# DC_IN.net
KiCad netlist of a schematic drawn in Altium Designer
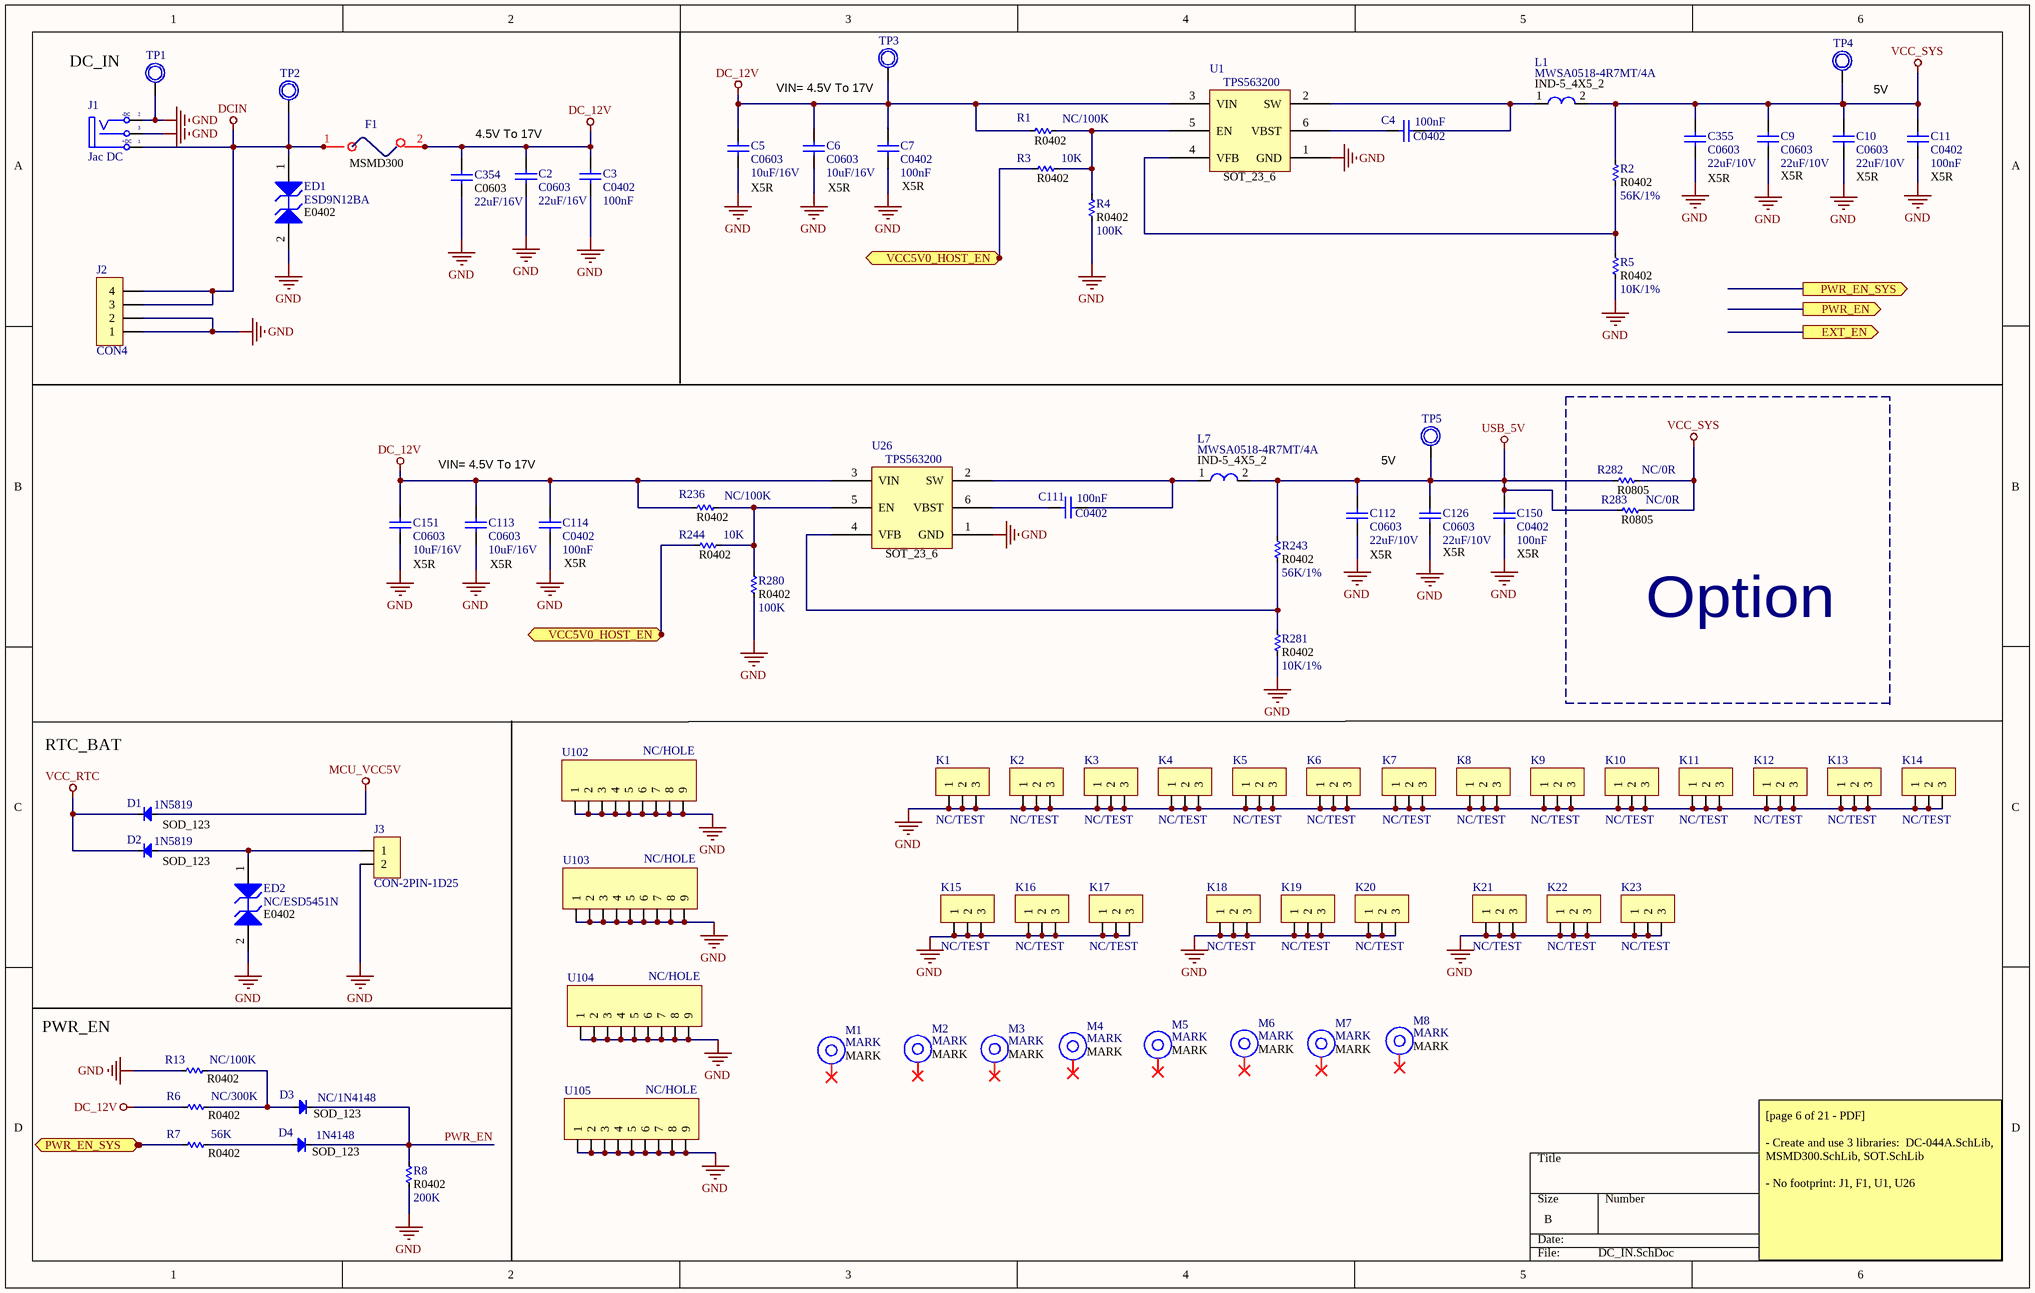
[diagram p0: DC_IN.SchDoc]

(export (version "E")
  (design (tool "Eeschema 10.0.6"))
  (components
    (comp (ref "C2")
      (value "C0603")
      (footprint "C 0603")
      (description "Capacitor")
      (fields (field (name "ALTIUM_VALUE") "22uF/16V") (field (name "PUBLISHER") "Altium Limited"))
      (libsource (lib "Miscellaneous Devices") (part "Cap"))
    )
    (comp (ref "C3")
      (value "C0402")
      (footprint "C 0402")
      (description "Capacitor")
      (fields (field (name "ALTIUM_VALUE") "100nF") (field (name "PUBLISHER") "Altium Limited"))
      (libsource (lib "Miscellaneous Devices") (part "Cap"))
    )
    (comp (ref "C4")
      (value "C0402")
      (footprint "C 0402")
      (description "Capacitor")
      (fields (field (name "ALTIUM_VALUE") "100nF") (field (name "PUBLISHER") "Altium Limited"))
      (libsource (lib "Miscellaneous Devices") (part "Cap"))
    )
    (comp (ref "C5")
      (value "C0603")
      (footprint "C 0603")
      (description "Capacitor")
      (fields
        (field (name "ALTIUM_VALUE") "10uF/16V")
        (field (name "ALTIUM_UNNAMED_1") "X5R")
        (field (name "PUBLISHER") "Altium Limited")
      )
      (libsource (lib "Miscellaneous Devices") (part "Cap"))
    )
    (comp (ref "C6")
      (value "C0603")
      (footprint "C 0603")
      (description "Capacitor")
      (fields
        (field (name "ALTIUM_VALUE") "10uF/16V")
        (field (name "ALTIUM_UNNAMED_1") "X5R")
        (field (name "PUBLISHER") "Altium Limited")
      )
      (libsource (lib "Miscellaneous Devices") (part "Cap"))
    )
    (comp (ref "C7")
      (value "C0402")
      (footprint "C 0402")
      (description "Capacitor")
      (fields
        (field (name "ALTIUM_VALUE") "100nF")
        (field (name "ALTIUM_UNNAMED_1") "X5R")
        (field (name "PUBLISHER") "Altium Limited")
      )
      (libsource (lib "Miscellaneous Devices") (part "Cap"))
    )
    (comp (ref "C9")
      (value "C0603")
      (footprint "C 0603")
      (description "Capacitor")
      (fields
        (field (name "ALTIUM_VALUE") "22uF/10V")
        (field (name "ALTIUM_UNNAMED_1") "X5R")
        (field (name "PUBLISHER") "Altium Limited")
      )
      (libsource (lib "Miscellaneous Devices") (part "Cap"))
    )
    (comp (ref "C10")
      (value "C0603")
      (footprint "C 0603")
      (description "Capacitor")
      (fields
        (field (name "ALTIUM_VALUE") "22uF/10V")
        (field (name "ALTIUM_UNNAMED_1") "X5R")
        (field (name "PUBLISHER") "Altium Limited")
      )
      (libsource (lib "Miscellaneous Devices") (part "Cap"))
    )
    (comp (ref "C11")
      (value "C0402")
      (footprint "C 0402")
      (description "Capacitor")
      (fields
        (field (name "ALTIUM_VALUE") "100nF")
        (field (name "ALTIUM_UNNAMED_1") "X5R")
        (field (name "PUBLISHER") "Altium Limited")
      )
      (libsource (lib "Miscellaneous Devices") (part "Cap"))
    )
    (comp (ref "C111")
      (value "C0402")
      (footprint "C 0402")
      (description "Capacitor")
      (fields (field (name "ALTIUM_VALUE") "100nF") (field (name "PUBLISHER") "Altium Limited"))
      (libsource (lib "Miscellaneous Devices") (part "Cap"))
    )
    (comp (ref "C112")
      (value "C0603")
      (footprint "C 0603")
      (description "Capacitor")
      (fields
        (field (name "ALTIUM_VALUE") "22uF/10V")
        (field (name "ALTIUM_UNNAMED_1") "X5R")
        (field (name "PUBLISHER") "Altium Limited")
      )
      (libsource (lib "Miscellaneous Devices") (part "Cap"))
    )
    (comp (ref "C113")
      (value "C0603")
      (footprint "C 0603")
      (description "Capacitor")
      (fields
        (field (name "ALTIUM_VALUE") "10uF/16V")
        (field (name "ALTIUM_UNNAMED_1") "X5R")
        (field (name "PUBLISHER") "Altium Limited")
      )
      (libsource (lib "Miscellaneous Devices") (part "Cap"))
    )
    (comp (ref "C114")
      (value "C0402")
      (footprint "C 0402")
      (description "Capacitor")
      (fields
        (field (name "ALTIUM_VALUE") "100nF")
        (field (name "ALTIUM_UNNAMED_1") "X5R")
        (field (name "PUBLISHER") "Altium Limited")
      )
      (libsource (lib "Miscellaneous Devices") (part "Cap"))
    )
    (comp (ref "C126")
      (value "C0603")
      (footprint "C 0603")
      (description "Capacitor")
      (fields
        (field (name "ALTIUM_VALUE") "22uF/10V")
        (field (name "ALTIUM_UNNAMED_1") "X5R")
        (field (name "PUBLISHER") "Altium Limited")
      )
      (libsource (lib "Miscellaneous Devices") (part "Cap"))
    )
    (comp (ref "C150")
      (value "C0402")
      (footprint "C 0402")
      (description "Capacitor")
      (fields
        (field (name "ALTIUM_VALUE") "100nF")
        (field (name "ALTIUM_UNNAMED_1") "X5R")
        (field (name "PUBLISHER") "Altium Limited")
      )
      (libsource (lib "Miscellaneous Devices") (part "Cap"))
    )
    (comp (ref "C151")
      (value "C0603")
      (footprint "C 0603")
      (description "Capacitor")
      (fields
        (field (name "ALTIUM_VALUE") "10uF/16V")
        (field (name "ALTIUM_UNNAMED_1") "X5R")
        (field (name "PUBLISHER") "Altium Limited")
      )
      (libsource (lib "Miscellaneous Devices") (part "Cap"))
    )
    (comp (ref "C354")
      (value "C0603")
      (footprint "C 0603")
      (description "Capacitor")
      (fields (field (name "ALTIUM_VALUE") "22uF/16V") (field (name "PUBLISHER") "Altium Limited"))
      (libsource (lib "Miscellaneous Devices") (part "Cap"))
    )
    (comp (ref "C355")
      (value "C0603")
      (footprint "C 0603")
      (description "Capacitor")
      (fields
        (field (name "ALTIUM_VALUE") "22uF/10V")
        (field (name "ALTIUM_UNNAMED_1") "X5R")
        (field (name "PUBLISHER") "Altium Limited")
      )
      (libsource (lib "Miscellaneous Devices") (part "Cap"))
    )
    (comp (ref "D1")
      (value "1N5819")
      (footprint "DIO-SMD-123")
      (description "Default Diode")
      (fields
        (field (name "TYPR") "SOD_123")
        (field (name "Comment") "Diode SMD")
        (field (name "PUBLISHER") "Altium Limited")
      )
      (libsource (lib "LIBRARY") (part "Diode SMD"))
    )
    (comp (ref "D2")
      (value "1N5819")
      (footprint "DIO-SMD-123")
      (description "Default Diode")
      (fields
        (field (name "TYPR") "SOD_123")
        (field (name "Comment") "Diode SMD")
        (field (name "PUBLISHER") "Altium Limited")
      )
      (libsource (lib "LIBRARY") (part "Diode SMD"))
    )
    (comp (ref "D3")
      (value "NC/1N4148")
      (footprint "DIO-SMD-123")
      (description "Default Diode")
      (fields
        (field (name "TYPR") "SOD_123")
        (field (name "Comment") "Diode SMD")
        (field (name "PUBLISHER") "Altium Limited")
      )
      (libsource (lib "LIBRARY") (part "Diode SMD"))
    )
    (comp (ref "D4")
      (value "1N4148")
      (footprint "DIO-SMD-123")
      (description "Default Diode")
      (fields
        (field (name "TYPR") "SOD_123")
        (field (name "Comment") "Diode SMD")
        (field (name "PUBLISHER") "Altium Limited")
      )
      (libsource (lib "LIBRARY") (part "Diode SMD"))
    )
    (comp (ref "ED1")
      (value "ESD9N12BA")
      (footprint "DFN1006:DFN1006-2L")
      (description "600 W Peak Power Zener Transient Voltage Suppressor, Bidirectional, 2-Pin SMB, Tape and Reel")
      (fields
        (field (name "MANUFACTURER") "On Semiconductor")
        (field (name "PARTNUMBER") "1SMB54CAT3")
        (field (name "SIZE") "E0402")
      )
      (libsource (lib "ON Semi Transient Voltage Suppressors (TVS)") (part "1SMB54CAT3"))
    )
    (comp (ref "ED2")
      (value "NC/ESD5451N")
      (footprint "DFN1006:DFN1006-2L")
      (description "600 W Peak Power Zener Transient Voltage Suppressor, Bidirectional, 2-Pin SMB, Tape and Reel")
      (fields
        (field (name "MANUFACTURER") "On Semiconductor")
        (field (name "PARTNUMBER") "1SMB54CAT3")
        (field (name "SIZE") "E0402")
      )
      (libsource (lib "ON Semi Transient Voltage Suppressors (TVS)") (part "1SMB54CAT3"))
    )
    (comp (ref "F1") (value "mSMD300") (footprint "MSMD300/3A") (libsource (lib "Schlib2") (part "mSMD300")))
    (comp (ref "J1")
      (value "Jac DC")
      (footprint "DC-IN")
      (description "Jac DC input")
      (libsource (lib "syhaunguyen") (part "DCIN"))
    )
    (comp (ref "J2")
      (value "CON4")
      (footprint "CON4")
      (description "WR-PHD 2.00 mm Socket Header")
      (fields
        (field (name "MANUFACTURER") "Würth Elektronik eiSos GmbH")
        (field (name "PARTNO") "62000411821")
        (field (name "CREATED BY") "Karrer Zheng")
      )
      (libsource (lib "LIBRARY") (part "JP4x1-2.0"))
    )
    (comp (ref "J3")
      (value "CON-2PIN-1D25")
      (footprint "Header2")
      (description "WR-PHD 2.54 mm Angled Socket Header")
      (fields
        (field (name "MANUFACTURER") "Würth Elektronik eiSos GmbH")
        (field (name "PARTNO") "613002143121")
        (field (name "CREATED BY") "Karrer Zheng")
      )
      (libsource (lib "LIBRARY") (part "JP2"))
    )
    (comp (ref "K1")
      (value "NC/TEST")
      (footprint "KTest")
      (description "WR-PHD 2.54 mm Angled Socket Header")
      (fields
        (field (name "MANUFACTURER") "Würth Elektronik eiSos GmbH")
        (field (name "PARTNO") "613003143121")
        (field (name "CREATED BY") "Karrer Zheng")
      )
      (libsource (lib "LIBRARY") (part "JP3"))
    )
    (comp (ref "K2")
      (value "NC/TEST")
      (footprint "KTest")
      (description "WR-PHD 2.54 mm Angled Socket Header")
      (fields
        (field (name "MANUFACTURER") "Würth Elektronik eiSos GmbH")
        (field (name "PARTNO") "613003143121")
        (field (name "CREATED BY") "Karrer Zheng")
      )
      (libsource (lib "LIBRARY") (part "JP3"))
    )
    (comp (ref "K3")
      (value "NC/TEST")
      (footprint "KTest")
      (description "WR-PHD 2.54 mm Angled Socket Header")
      (fields
        (field (name "MANUFACTURER") "Würth Elektronik eiSos GmbH")
        (field (name "PARTNO") "613003143121")
        (field (name "CREATED BY") "Karrer Zheng")
      )
      (libsource (lib "LIBRARY") (part "JP3"))
    )
    (comp (ref "K4")
      (value "NC/TEST")
      (footprint "KTest")
      (description "WR-PHD 2.54 mm Angled Socket Header")
      (fields
        (field (name "MANUFACTURER") "Würth Elektronik eiSos GmbH")
        (field (name "PARTNO") "613003143121")
        (field (name "CREATED BY") "Karrer Zheng")
      )
      (libsource (lib "LIBRARY") (part "JP3"))
    )
    (comp (ref "K5")
      (value "NC/TEST")
      (footprint "KTest")
      (description "WR-PHD 2.54 mm Angled Socket Header")
      (fields
        (field (name "MANUFACTURER") "Würth Elektronik eiSos GmbH")
        (field (name "PARTNO") "613003143121")
        (field (name "CREATED BY") "Karrer Zheng")
      )
      (libsource (lib "LIBRARY") (part "JP3"))
    )
    (comp (ref "K6")
      (value "NC/TEST")
      (footprint "KTest")
      (description "WR-PHD 2.54 mm Angled Socket Header")
      (fields
        (field (name "MANUFACTURER") "Würth Elektronik eiSos GmbH")
        (field (name "PARTNO") "613003143121")
        (field (name "CREATED BY") "Karrer Zheng")
      )
      (libsource (lib "LIBRARY") (part "JP3"))
    )
    (comp (ref "K7")
      (value "NC/TEST")
      (footprint "KTest")
      (description "WR-PHD 2.54 mm Angled Socket Header")
      (fields
        (field (name "MANUFACTURER") "Würth Elektronik eiSos GmbH")
        (field (name "PARTNO") "613003143121")
        (field (name "CREATED BY") "Karrer Zheng")
      )
      (libsource (lib "LIBRARY") (part "JP3"))
    )
    (comp (ref "K8")
      (value "NC/TEST")
      (footprint "KTest")
      (description "WR-PHD 2.54 mm Angled Socket Header")
      (fields
        (field (name "MANUFACTURER") "Würth Elektronik eiSos GmbH")
        (field (name "PARTNO") "613003143121")
        (field (name "CREATED BY") "Karrer Zheng")
      )
      (libsource (lib "LIBRARY") (part "JP3"))
    )
    (comp (ref "K9")
      (value "NC/TEST")
      (footprint "KTest")
      (description "WR-PHD 2.54 mm Angled Socket Header")
      (fields
        (field (name "MANUFACTURER") "Würth Elektronik eiSos GmbH")
        (field (name "PARTNO") "613003143121")
        (field (name "CREATED BY") "Karrer Zheng")
      )
      (libsource (lib "LIBRARY") (part "JP3"))
    )
    (comp (ref "K10")
      (value "NC/TEST")
      (footprint "KTest")
      (description "WR-PHD 2.54 mm Angled Socket Header")
      (fields
        (field (name "MANUFACTURER") "Würth Elektronik eiSos GmbH")
        (field (name "PARTNO") "613003143121")
        (field (name "CREATED BY") "Karrer Zheng")
      )
      (libsource (lib "LIBRARY") (part "JP3"))
    )
    (comp (ref "K11")
      (value "NC/TEST")
      (footprint "KTest")
      (description "WR-PHD 2.54 mm Angled Socket Header")
      (fields
        (field (name "MANUFACTURER") "Würth Elektronik eiSos GmbH")
        (field (name "PARTNO") "613003143121")
        (field (name "CREATED BY") "Karrer Zheng")
      )
      (libsource (lib "LIBRARY") (part "JP3"))
    )
    (comp (ref "K12")
      (value "NC/TEST")
      (footprint "KTest")
      (description "WR-PHD 2.54 mm Angled Socket Header")
      (fields
        (field (name "MANUFACTURER") "Würth Elektronik eiSos GmbH")
        (field (name "PARTNO") "613003143121")
        (field (name "CREATED BY") "Karrer Zheng")
      )
      (libsource (lib "LIBRARY") (part "JP3"))
    )
    (comp (ref "K13")
      (value "NC/TEST")
      (footprint "KTest")
      (description "WR-PHD 2.54 mm Angled Socket Header")
      (fields
        (field (name "MANUFACTURER") "Würth Elektronik eiSos GmbH")
        (field (name "PARTNO") "613003143121")
        (field (name "CREATED BY") "Karrer Zheng")
      )
      (libsource (lib "LIBRARY") (part "JP3"))
    )
    (comp (ref "K14")
      (value "NC/TEST")
      (footprint "KTest")
      (description "WR-PHD 2.54 mm Angled Socket Header")
      (fields
        (field (name "MANUFACTURER") "Würth Elektronik eiSos GmbH")
        (field (name "PARTNO") "613003143121")
        (field (name "CREATED BY") "Karrer Zheng")
      )
      (libsource (lib "LIBRARY") (part "JP3"))
    )
    (comp (ref "K15")
      (value "NC/TEST")
      (footprint "KTest")
      (description "WR-PHD 2.54 mm Angled Socket Header")
      (fields
        (field (name "MANUFACTURER") "Würth Elektronik eiSos GmbH")
        (field (name "PARTNO") "613003143121")
        (field (name "CREATED BY") "Karrer Zheng")
      )
      (libsource (lib "LIBRARY") (part "JP3"))
    )
    (comp (ref "K16")
      (value "NC/TEST")
      (footprint "KTest")
      (description "WR-PHD 2.54 mm Angled Socket Header")
      (fields
        (field (name "MANUFACTURER") "Würth Elektronik eiSos GmbH")
        (field (name "PARTNO") "613003143121")
        (field (name "CREATED BY") "Karrer Zheng")
      )
      (libsource (lib "LIBRARY") (part "JP3"))
    )
    (comp (ref "K17")
      (value "NC/TEST")
      (footprint "KTest")
      (description "WR-PHD 2.54 mm Angled Socket Header")
      (fields
        (field (name "MANUFACTURER") "Würth Elektronik eiSos GmbH")
        (field (name "PARTNO") "613003143121")
        (field (name "CREATED BY") "Karrer Zheng")
      )
      (libsource (lib "LIBRARY") (part "JP3"))
    )
    (comp (ref "K18")
      (value "NC/TEST")
      (footprint "KTest")
      (description "WR-PHD 2.54 mm Angled Socket Header")
      (fields
        (field (name "MANUFACTURER") "Würth Elektronik eiSos GmbH")
        (field (name "PARTNO") "613003143121")
        (field (name "CREATED BY") "Karrer Zheng")
      )
      (libsource (lib "LIBRARY") (part "JP3"))
    )
    (comp (ref "K19")
      (value "NC/TEST")
      (footprint "KTest")
      (description "WR-PHD 2.54 mm Angled Socket Header")
      (fields
        (field (name "MANUFACTURER") "Würth Elektronik eiSos GmbH")
        (field (name "PARTNO") "613003143121")
        (field (name "CREATED BY") "Karrer Zheng")
      )
      (libsource (lib "LIBRARY") (part "JP3"))
    )
    (comp (ref "K20")
      (value "NC/TEST")
      (footprint "KTest")
      (description "WR-PHD 2.54 mm Angled Socket Header")
      (fields
        (field (name "MANUFACTURER") "Würth Elektronik eiSos GmbH")
        (field (name "PARTNO") "613003143121")
        (field (name "CREATED BY") "Karrer Zheng")
      )
      (libsource (lib "LIBRARY") (part "JP3"))
    )
    (comp (ref "K21")
      (value "NC/TEST")
      (footprint "KTest")
      (description "WR-PHD 2.54 mm Angled Socket Header")
      (fields
        (field (name "MANUFACTURER") "Würth Elektronik eiSos GmbH")
        (field (name "PARTNO") "613003143121")
        (field (name "CREATED BY") "Karrer Zheng")
      )
      (libsource (lib "LIBRARY") (part "JP3"))
    )
    (comp (ref "K22")
      (value "NC/TEST")
      (footprint "KTest")
      (description "WR-PHD 2.54 mm Angled Socket Header")
      (fields
        (field (name "MANUFACTURER") "Würth Elektronik eiSos GmbH")
        (field (name "PARTNO") "613003143121")
        (field (name "CREATED BY") "Karrer Zheng")
      )
      (libsource (lib "LIBRARY") (part "JP3"))
    )
    (comp (ref "K23")
      (value "NC/TEST")
      (footprint "KTest")
      (description "WR-PHD 2.54 mm Angled Socket Header")
      (fields
        (field (name "MANUFACTURER") "Würth Elektronik eiSos GmbH")
        (field (name "PARTNO") "613003143121")
        (field (name "CREATED BY") "Karrer Zheng")
      )
      (libsource (lib "LIBRARY") (part "JP3"))
    )
    (comp (ref "L1")
      (value "MWSA0518-4R7MT/4A")
      (footprint "L-SMD-M-7.3x4.5")
      (fields
        (field (name "PARTNO") "78477010")
        (field (name "MANUFACTURER") "Wurth Elektronik")
        (field (name "ALTIUM_UNNAMED_1") "IND-5_4X5_2")
        (field (name "CREATED BY") "Baojun Chen")
      )
      (libsource (lib "LIBRARY") (part "L-SMD-1"))
    )
    (comp (ref "L7")
      (value "MWSA0518-4R7MT/4A")
      (footprint "L-SMD-M-7.3x4.5")
      (fields
        (field (name "PARTNO") "78477010")
        (field (name "MANUFACTURER") "Wurth Elektronik")
        (field (name "ALTIUM_UNNAMED_1") "IND-5_4X5_2")
        (field (name "CREATED BY") "Baojun Chen")
      )
      (libsource (lib "LIBRARY") (part "L-SMD-1"))
    )
    (comp (ref "M1") (value "MARK") (libsource (lib "SOT") (part "MARK")))
    (comp (ref "M2") (value "MARK") (libsource (lib "SOT") (part "MARK")))
    (comp (ref "M3") (value "MARK") (libsource (lib "SOT") (part "MARK")))
    (comp (ref "M4") (value "MARK") (libsource (lib "SOT") (part "MARK")))
    (comp (ref "M5") (value "MARK") (libsource (lib "SOT") (part "MARK")))
    (comp (ref "M6") (value "MARK") (libsource (lib "SOT") (part "MARK")))
    (comp (ref "M7") (value "MARK") (libsource (lib "SOT") (part "MARK")))
    (comp (ref "M8") (value "MARK") (libsource (lib "SOT") (part "MARK")))
    (comp (ref "R1")
      (value "R0402")
      (footprint "R 0402")
      (description "Resistor")
      (fields
        (field (name "MANUFACTURER") "Generic Components")
        (field (name "ALTIUM_VALUE") "NC/100K")
        (field (name "PUBLISHER") "Altium Hobart Technology Centre")
      )
      (libsource (lib "LIBRARY") (part "Res-SMD"))
    )
    (comp (ref "R2")
      (value "R0402")
      (footprint "R 0402")
      (description "Resistor")
      (fields
        (field (name "MANUFACTURER") "Generic Components")
        (field (name "ALTIUM_VALUE") "56K/1%")
        (field (name "PUBLISHER") "Altium Hobart Technology Centre")
      )
      (libsource (lib "LIBRARY") (part "Res-SMD"))
    )
    (comp (ref "R3")
      (value "R0402")
      (footprint "R 0402")
      (description "Resistor")
      (fields
        (field (name "MANUFACTURER") "Generic Components")
        (field (name "ALTIUM_VALUE") "10K")
        (field (name "PUBLISHER") "Altium Hobart Technology Centre")
      )
      (libsource (lib "LIBRARY") (part "Res-SMD"))
    )
    (comp (ref "R4")
      (value "R0402")
      (footprint "R 0402")
      (description "Resistor")
      (fields
        (field (name "MANUFACTURER") "Generic Components")
        (field (name "ALTIUM_VALUE") "100K")
        (field (name "PUBLISHER") "Altium Hobart Technology Centre")
      )
      (libsource (lib "LIBRARY") (part "Res-SMD"))
    )
    (comp (ref "R5")
      (value "R0402")
      (footprint "R 0402")
      (description "Resistor")
      (fields
        (field (name "MANUFACTURER") "Generic Components")
        (field (name "ALTIUM_VALUE") "10K/1%")
        (field (name "PUBLISHER") "Altium Hobart Technology Centre")
      )
      (libsource (lib "LIBRARY") (part "Res-SMD"))
    )
    (comp (ref "R6")
      (value "R0402")
      (footprint "R 0402")
      (description "Resistor")
      (fields
        (field (name "MANUFACTURER") "Generic Components")
        (field (name "ALTIUM_VALUE") "NC/300K")
        (field (name "PUBLISHER") "Altium Hobart Technology Centre")
      )
      (libsource (lib "LIBRARY") (part "Res-SMD"))
    )
    (comp (ref "R7")
      (value "R0402")
      (footprint "R 0402")
      (description "Resistor")
      (fields
        (field (name "MANUFACTURER") "Generic Components")
        (field (name "ALTIUM_VALUE") "56K")
        (field (name "PUBLISHER") "Altium Hobart Technology Centre")
      )
      (libsource (lib "LIBRARY") (part "Res-SMD"))
    )
    (comp (ref "R8")
      (value "R0402")
      (footprint "R 0402")
      (description "Resistor")
      (fields
        (field (name "MANUFACTURER") "Generic Components")
        (field (name "ALTIUM_VALUE") "200K")
        (field (name "PUBLISHER") "Altium Hobart Technology Centre")
      )
      (libsource (lib "LIBRARY") (part "Res-SMD"))
    )
    (comp (ref "R13")
      (value "R0402")
      (footprint "R 0402")
      (description "Resistor")
      (fields
        (field (name "MANUFACTURER") "Generic Components")
        (field (name "ALTIUM_VALUE") "NC/100K")
        (field (name "PUBLISHER") "Altium Hobart Technology Centre")
      )
      (libsource (lib "LIBRARY") (part "Res-SMD"))
    )
    (comp (ref "R236")
      (value "R0402")
      (footprint "R 0402")
      (description "Resistor")
      (fields
        (field (name "MANUFACTURER") "Generic Components")
        (field (name "ALTIUM_VALUE") "NC/100K")
        (field (name "PUBLISHER") "Altium Hobart Technology Centre")
      )
      (libsource (lib "LIBRARY") (part "Res-SMD"))
    )
    (comp (ref "R243")
      (value "R0402")
      (footprint "R 0402")
      (description "Resistor")
      (fields
        (field (name "MANUFACTURER") "Generic Components")
        (field (name "ALTIUM_VALUE") "56K/1%")
        (field (name "PUBLISHER") "Altium Hobart Technology Centre")
      )
      (libsource (lib "LIBRARY") (part "Res-SMD"))
    )
    (comp (ref "R244")
      (value "R0402")
      (footprint "R 0402")
      (description "Resistor")
      (fields
        (field (name "MANUFACTURER") "Generic Components")
        (field (name "ALTIUM_VALUE") "10K")
        (field (name "PUBLISHER") "Altium Hobart Technology Centre")
      )
      (libsource (lib "LIBRARY") (part "Res-SMD"))
    )
    (comp (ref "R280")
      (value "R0402")
      (footprint "R 0402")
      (description "Resistor")
      (fields
        (field (name "MANUFACTURER") "Generic Components")
        (field (name "ALTIUM_VALUE") "100K")
        (field (name "PUBLISHER") "Altium Hobart Technology Centre")
      )
      (libsource (lib "LIBRARY") (part "Res-SMD"))
    )
    (comp (ref "R281")
      (value "R0402")
      (footprint "R 0402")
      (description "Resistor")
      (fields
        (field (name "MANUFACTURER") "Generic Components")
        (field (name "ALTIUM_VALUE") "10K/1%")
        (field (name "PUBLISHER") "Altium Hobart Technology Centre")
      )
      (libsource (lib "LIBRARY") (part "Res-SMD"))
    )
    (comp (ref "R282")
      (value "R0805")
      (footprint "R 0805")
      (description "Resistor")
      (fields
        (field (name "MANUFACTURER") "Generic Components")
        (field (name "ALTIUM_VALUE") "NC/0R")
        (field (name "PUBLISHER") "Altium Hobart Technology Centre")
      )
      (libsource (lib "LIBRARY") (part "Res-SMD"))
    )
    (comp (ref "R283")
      (value "R0805")
      (footprint "R 0805")
      (description "Resistor")
      (fields
        (field (name "MANUFACTURER") "Generic Components")
        (field (name "ALTIUM_VALUE") "NC/0R")
        (field (name "PUBLISHER") "Altium Hobart Technology Centre")
      )
      (libsource (lib "LIBRARY") (part "Res-SMD"))
    )
    (comp (ref "TP1")
      (value "TP")
      (footprint "TP1")
      (description "Test Point")
      (libsource (lib "syhaunguyen") (part "TP1"))
    )
    (comp (ref "TP2")
      (value "TP")
      (footprint "TP1")
      (description "Test Point")
      (libsource (lib "syhaunguyen") (part "TP1"))
    )
    (comp (ref "TP3")
      (value "TP")
      (footprint "TP1")
      (description "Test Point")
      (libsource (lib "syhaunguyen") (part "TP1"))
    )
    (comp (ref "TP4")
      (value "TP")
      (footprint "TP1")
      (description "Test Point")
      (libsource (lib "syhaunguyen") (part "TP1"))
    )
    (comp (ref "TP5")
      (value "TP")
      (footprint "TP1")
      (description "Test Point")
      (libsource (lib "syhaunguyen") (part "TP1"))
    )
    (comp (ref "U1")
      (value "SOT-23-6_TPS563200")
      (footprint "SOT:SOT-23-6")
      (description "Switching Voltage Regulators 17 Vin,3A Sync SD Reg")
      (fields
        (field (name "MANUFACTURER") "Texas Instruments")
        (field (name "MANUFACTURER PART NUMBER") "TPS563200DDCR")
      )
      (libsource (lib "SOT") (part "SOT-23-6_TPS563200"))
    )
    (comp (ref "U26")
      (value "SOT-23-6_TPS563200")
      (footprint "SOT:SOT-23-6")
      (description "Switching Voltage Regulators 17 Vin,3A Sync SD Reg")
      (fields
        (field (name "MANUFACTURER") "Texas Instruments")
        (field (name "MANUFACTURER PART NUMBER") "TPS563200DDCR")
      )
      (libsource (lib "SOT") (part "SOT-23-6_TPS563200"))
    )
    (comp (ref "U102")
      (value "NC/HOLE")
      (footprint "JP9-C1T")
      (description "WR-PHD 2.54 mm Angled Socket Header")
      (fields
        (field (name "MANUFACTURER") "Würth Elektronik eiSos GmbH")
        (field (name "PARTNO") "613009143121")
        (field (name "CREATED BY") "Karrer Zheng")
      )
      (libsource (lib "LIBRARY") (part "JP9"))
    )
    (comp (ref "U103")
      (value "NC/HOLE")
      (footprint "JP9-C1T")
      (description "WR-PHD 2.54 mm Angled Socket Header")
      (fields
        (field (name "MANUFACTURER") "Würth Elektronik eiSos GmbH")
        (field (name "PARTNO") "613009143121")
        (field (name "CREATED BY") "Karrer Zheng")
      )
      (libsource (lib "LIBRARY") (part "JP9"))
    )
    (comp (ref "U104")
      (value "NC/HOLE")
      (footprint "JP9-C1T")
      (description "WR-PHD 2.54 mm Angled Socket Header")
      (fields
        (field (name "MANUFACTURER") "Würth Elektronik eiSos GmbH")
        (field (name "PARTNO") "613009143121")
        (field (name "CREATED BY") "Karrer Zheng")
      )
      (libsource (lib "LIBRARY") (part "JP9"))
    )
    (comp (ref "U105")
      (value "NC/HOLE")
      (footprint "JP9-C1T")
      (description "WR-PHD 2.54 mm Angled Socket Header")
      (fields
        (field (name "MANUFACTURER") "Würth Elektronik eiSos GmbH")
        (field (name "PARTNO") "613009143121")
        (field (name "CREATED BY") "Karrer Zheng")
      )
      (libsource (lib "LIBRARY") (part "JP9"))
    )
  )
  (nets
    (net (code "2") (name "/PWR_EN") (class "Default")
      (node (ref "D3") (pin "2") (pinfunction "K_2") (pintype "passive"))
      (node (ref "D4") (pin "2") (pinfunction "K_2") (pintype "passive"))
      (node (ref "R8") (pin "1") (pinfunction "1_1") (pintype "passive"))
    )
    (net (code "3") (name "/PWR_EN_SYS") (class "Default")
      (node (ref "R7") (pin "2") (pinfunction "2_2") (pintype "passive"))
    )
    (net (code "5") (name "DCIN") (class "Default")
      (node (ref "ED1") (pin "1") (pinfunction "A1_1") (pintype "passive"))
      (node (ref "F1") (pin "1") (pinfunction "1_1") (pintype "passive"))
      (node (ref "J1") (pin "1") (pinfunction "T_1") (pintype "passive"))
      (node (ref "J2") (pin "3") (pinfunction "3_3") (pintype "passive"))
      (node (ref "J2") (pin "4") (pinfunction "4_4") (pintype "passive"))
      (node (ref "TP2") (pin "1") (pinfunction "1_1") (pintype "passive"))
    )
    (net (code "6") (name "DC_12V") (class "Default")
      (node (ref "C113") (pin "2") (pinfunction "2_2") (pintype "passive"))
      (node (ref "C114") (pin "2") (pinfunction "2_2") (pintype "passive"))
      (node (ref "C151") (pin "2") (pinfunction "2_2") (pintype "passive"))
      (node (ref "C2") (pin "2") (pinfunction "2_2") (pintype "passive"))
      (node (ref "C3") (pin "2") (pinfunction "2_2") (pintype "passive"))
      (node (ref "C354") (pin "2") (pinfunction "2_2") (pintype "passive"))
      (node (ref "C5") (pin "2") (pinfunction "2_2") (pintype "passive"))
      (node (ref "C6") (pin "2") (pinfunction "2_2") (pintype "passive"))
      (node (ref "C7") (pin "2") (pinfunction "2_2") (pintype "passive"))
      (node (ref "F1") (pin "2") (pinfunction "2_2") (pintype "passive"))
      (node (ref "R1") (pin "2") (pinfunction "2_2") (pintype "passive"))
      (node (ref "R236") (pin "2") (pinfunction "2_2") (pintype "passive"))
      (node (ref "R6") (pin "2") (pinfunction "2_2") (pintype "passive"))
      (node (ref "TP3") (pin "1") (pinfunction "1_1") (pintype "passive"))
      (node (ref "U1") (pin "3") (pinfunction "VIN_3") (pintype "passive"))
      (node (ref "U26") (pin "3") (pinfunction "VIN_3") (pintype "passive"))
    )
    (net (code "7") (name "GND") (class "Default")
      (node (ref "C10") (pin "1") (pinfunction "1_1") (pintype "passive"))
      (node (ref "C11") (pin "1") (pinfunction "1_1") (pintype "passive"))
      (node (ref "C112") (pin "1") (pinfunction "1_1") (pintype "passive"))
      (node (ref "C113") (pin "1") (pinfunction "1_1") (pintype "passive"))
      (node (ref "C114") (pin "1") (pinfunction "1_1") (pintype "passive"))
      (node (ref "C126") (pin "1") (pinfunction "1_1") (pintype "passive"))
      (node (ref "C150") (pin "1") (pinfunction "1_1") (pintype "passive"))
      (node (ref "C151") (pin "1") (pinfunction "1_1") (pintype "passive"))
      (node (ref "C2") (pin "1") (pinfunction "1_1") (pintype "passive"))
      (node (ref "C3") (pin "1") (pinfunction "1_1") (pintype "passive"))
      (node (ref "C354") (pin "1") (pinfunction "1_1") (pintype "passive"))
      (node (ref "C355") (pin "1") (pinfunction "1_1") (pintype "passive"))
      (node (ref "C5") (pin "1") (pinfunction "1_1") (pintype "passive"))
      (node (ref "C6") (pin "1") (pinfunction "1_1") (pintype "passive"))
      (node (ref "C7") (pin "1") (pinfunction "1_1") (pintype "passive"))
      (node (ref "C9") (pin "1") (pinfunction "1_1") (pintype "passive"))
      (node (ref "ED1") (pin "2") (pinfunction "A2_2") (pintype "passive"))
      (node (ref "ED2") (pin "2") (pinfunction "A2_2") (pintype "passive"))
      (node (ref "J1") (pin "2") (pinfunction "TN_2") (pintype "passive"))
      (node (ref "J1") (pin "3") (pinfunction "S_3") (pintype "power_in"))
      (node (ref "J2") (pin "1") (pinfunction "1_1") (pintype "passive"))
      (node (ref "J2") (pin "2") (pinfunction "2_2") (pintype "passive"))
      (node (ref "J3") (pin "2") (pinfunction "2_2") (pintype "passive"))
      (node (ref "K1") (pin "1") (pinfunction "1_1") (pintype "passive"))
      (node (ref "K1") (pin "2") (pinfunction "2_2") (pintype "passive"))
      (node (ref "K1") (pin "3") (pinfunction "3_3") (pintype "passive"))
      (node (ref "K10") (pin "1") (pinfunction "1_1") (pintype "passive"))
      (node (ref "K10") (pin "2") (pinfunction "2_2") (pintype "passive"))
      (node (ref "K10") (pin "3") (pinfunction "3_3") (pintype "passive"))
      (node (ref "K11") (pin "1") (pinfunction "1_1") (pintype "passive"))
      (node (ref "K11") (pin "2") (pinfunction "2_2") (pintype "passive"))
      (node (ref "K11") (pin "3") (pinfunction "3_3") (pintype "passive"))
      (node (ref "K12") (pin "1") (pinfunction "1_1") (pintype "passive"))
      (node (ref "K12") (pin "2") (pinfunction "2_2") (pintype "passive"))
      (node (ref "K12") (pin "3") (pinfunction "3_3") (pintype "passive"))
      (node (ref "K13") (pin "1") (pinfunction "1_1") (pintype "passive"))
      (node (ref "K13") (pin "2") (pinfunction "2_2") (pintype "passive"))
      (node (ref "K13") (pin "3") (pinfunction "3_3") (pintype "passive"))
      (node (ref "K14") (pin "1") (pinfunction "1_1") (pintype "passive"))
      (node (ref "K14") (pin "2") (pinfunction "2_2") (pintype "passive"))
      (node (ref "K14") (pin "3") (pinfunction "3_3") (pintype "passive"))
      (node (ref "K15") (pin "1") (pinfunction "1_1") (pintype "passive"))
      (node (ref "K15") (pin "2") (pinfunction "2_2") (pintype "passive"))
      (node (ref "K15") (pin "3") (pinfunction "3_3") (pintype "passive"))
      (node (ref "K16") (pin "1") (pinfunction "1_1") (pintype "passive"))
      (node (ref "K16") (pin "2") (pinfunction "2_2") (pintype "passive"))
      (node (ref "K16") (pin "3") (pinfunction "3_3") (pintype "passive"))
      (node (ref "K17") (pin "1") (pinfunction "1_1") (pintype "passive"))
      (node (ref "K17") (pin "2") (pinfunction "2_2") (pintype "passive"))
      (node (ref "K17") (pin "3") (pinfunction "3_3") (pintype "passive"))
      (node (ref "K18") (pin "1") (pinfunction "1_1") (pintype "passive"))
      (node (ref "K18") (pin "2") (pinfunction "2_2") (pintype "passive"))
      (node (ref "K18") (pin "3") (pinfunction "3_3") (pintype "passive"))
      (node (ref "K19") (pin "1") (pinfunction "1_1") (pintype "passive"))
      (node (ref "K19") (pin "2") (pinfunction "2_2") (pintype "passive"))
      (node (ref "K19") (pin "3") (pinfunction "3_3") (pintype "passive"))
      (node (ref "K2") (pin "1") (pinfunction "1_1") (pintype "passive"))
      (node (ref "K2") (pin "2") (pinfunction "2_2") (pintype "passive"))
      (node (ref "K2") (pin "3") (pinfunction "3_3") (pintype "passive"))
      (node (ref "K20") (pin "1") (pinfunction "1_1") (pintype "passive"))
      (node (ref "K20") (pin "2") (pinfunction "2_2") (pintype "passive"))
      (node (ref "K20") (pin "3") (pinfunction "3_3") (pintype "passive"))
      (node (ref "K21") (pin "1") (pinfunction "1_1") (pintype "passive"))
      (node (ref "K21") (pin "2") (pinfunction "2_2") (pintype "passive"))
      (node (ref "K21") (pin "3") (pinfunction "3_3") (pintype "passive"))
      (node (ref "K22") (pin "1") (pinfunction "1_1") (pintype "passive"))
      (node (ref "K22") (pin "2") (pinfunction "2_2") (pintype "passive"))
      (node (ref "K22") (pin "3") (pinfunction "3_3") (pintype "passive"))
      (node (ref "K23") (pin "1") (pinfunction "1_1") (pintype "passive"))
      (node (ref "K23") (pin "2") (pinfunction "2_2") (pintype "passive"))
      (node (ref "K23") (pin "3") (pinfunction "3_3") (pintype "passive"))
      (node (ref "K3") (pin "1") (pinfunction "1_1") (pintype "passive"))
      (node (ref "K3") (pin "2") (pinfunction "2_2") (pintype "passive"))
      (node (ref "K3") (pin "3") (pinfunction "3_3") (pintype "passive"))
      (node (ref "K4") (pin "1") (pinfunction "1_1") (pintype "passive"))
      (node (ref "K4") (pin "2") (pinfunction "2_2") (pintype "passive"))
      (node (ref "K4") (pin "3") (pinfunction "3_3") (pintype "passive"))
      (node (ref "K5") (pin "1") (pinfunction "1_1") (pintype "passive"))
      (node (ref "K5") (pin "2") (pinfunction "2_2") (pintype "passive"))
      (node (ref "K5") (pin "3") (pinfunction "3_3") (pintype "passive"))
      (node (ref "K6") (pin "1") (pinfunction "1_1") (pintype "passive"))
      (node (ref "K6") (pin "2") (pinfunction "2_2") (pintype "passive"))
      (node (ref "K6") (pin "3") (pinfunction "3_3") (pintype "passive"))
      (node (ref "K7") (pin "1") (pinfunction "1_1") (pintype "passive"))
      (node (ref "K7") (pin "2") (pinfunction "2_2") (pintype "passive"))
      (node (ref "K7") (pin "3") (pinfunction "3_3") (pintype "passive"))
      (node (ref "K8") (pin "1") (pinfunction "1_1") (pintype "passive"))
      (node (ref "K8") (pin "2") (pinfunction "2_2") (pintype "passive"))
      (node (ref "K8") (pin "3") (pinfunction "3_3") (pintype "passive"))
      (node (ref "K9") (pin "1") (pinfunction "1_1") (pintype "passive"))
      (node (ref "K9") (pin "2") (pinfunction "2_2") (pintype "passive"))
      (node (ref "K9") (pin "3") (pinfunction "3_3") (pintype "passive"))
      (node (ref "R13") (pin "2") (pinfunction "2_2") (pintype "passive"))
      (node (ref "R280") (pin "1") (pinfunction "1_1") (pintype "passive"))
      (node (ref "R281") (pin "2") (pinfunction "2_2") (pintype "passive"))
      (node (ref "R4") (pin "1") (pinfunction "1_1") (pintype "passive"))
      (node (ref "R5") (pin "2") (pinfunction "2_2") (pintype "passive"))
      (node (ref "R8") (pin "2") (pinfunction "2_2") (pintype "passive"))
      (node (ref "TP1") (pin "1") (pinfunction "1_1") (pintype "passive"))
      (node (ref "U1") (pin "1") (pinfunction "GND_1") (pintype "passive"))
      (node (ref "U102") (pin "1") (pinfunction "1_1") (pintype "passive"))
      (node (ref "U102") (pin "2") (pinfunction "2_2") (pintype "passive"))
      (node (ref "U102") (pin "3") (pinfunction "3_3") (pintype "passive"))
      (node (ref "U102") (pin "4") (pinfunction "4_4") (pintype "passive"))
      (node (ref "U102") (pin "5") (pinfunction "5_5") (pintype "passive"))
      (node (ref "U102") (pin "6") (pinfunction "6_6") (pintype "passive"))
      (node (ref "U102") (pin "7") (pinfunction "7_7") (pintype "passive"))
      (node (ref "U102") (pin "8") (pinfunction "8_8") (pintype "passive"))
      (node (ref "U102") (pin "9") (pinfunction "9_9") (pintype "passive"))
      (node (ref "U103") (pin "1") (pinfunction "1_1") (pintype "passive"))
      (node (ref "U103") (pin "2") (pinfunction "2_2") (pintype "passive"))
      (node (ref "U103") (pin "3") (pinfunction "3_3") (pintype "passive"))
      (node (ref "U103") (pin "4") (pinfunction "4_4") (pintype "passive"))
      (node (ref "U103") (pin "5") (pinfunction "5_5") (pintype "passive"))
      (node (ref "U103") (pin "6") (pinfunction "6_6") (pintype "passive"))
      (node (ref "U103") (pin "7") (pinfunction "7_7") (pintype "passive"))
      (node (ref "U103") (pin "8") (pinfunction "8_8") (pintype "passive"))
      (node (ref "U103") (pin "9") (pinfunction "9_9") (pintype "passive"))
      (node (ref "U104") (pin "1") (pinfunction "1_1") (pintype "passive"))
      (node (ref "U104") (pin "2") (pinfunction "2_2") (pintype "passive"))
      (node (ref "U104") (pin "3") (pinfunction "3_3") (pintype "passive"))
      (node (ref "U104") (pin "4") (pinfunction "4_4") (pintype "passive"))
      (node (ref "U104") (pin "5") (pinfunction "5_5") (pintype "passive"))
      (node (ref "U104") (pin "6") (pinfunction "6_6") (pintype "passive"))
      (node (ref "U104") (pin "7") (pinfunction "7_7") (pintype "passive"))
      (node (ref "U104") (pin "8") (pinfunction "8_8") (pintype "passive"))
      (node (ref "U104") (pin "9") (pinfunction "9_9") (pintype "passive"))
      (node (ref "U105") (pin "1") (pinfunction "1_1") (pintype "passive"))
      (node (ref "U105") (pin "2") (pinfunction "2_2") (pintype "passive"))
      (node (ref "U105") (pin "3") (pinfunction "3_3") (pintype "passive"))
      (node (ref "U105") (pin "4") (pinfunction "4_4") (pintype "passive"))
      (node (ref "U105") (pin "5") (pinfunction "5_5") (pintype "passive"))
      (node (ref "U105") (pin "6") (pinfunction "6_6") (pintype "passive"))
      (node (ref "U105") (pin "7") (pinfunction "7_7") (pintype "passive"))
      (node (ref "U105") (pin "8") (pinfunction "8_8") (pintype "passive"))
      (node (ref "U105") (pin "9") (pinfunction "9_9") (pintype "passive"))
      (node (ref "U26") (pin "1") (pinfunction "GND_1") (pintype "passive"))
    )
    (net (code "8") (name "MCU_VCC5V") (class "Default")
      (node (ref "D1") (pin "1") (pinfunction "A_1") (pintype "passive"))
    )
    (net (code "9") (name "Net-(D2-A)") (class "Default")
      (node (ref "D2") (pin "1") (pinfunction "A_1") (pintype "passive"))
      (node (ref "ED2") (pin "1") (pinfunction "A1_1") (pintype "passive"))
      (node (ref "J3") (pin "1") (pinfunction "1_1") (pintype "passive"))
    )
    (net (code "10") (name "Net-(D3-A)") (class "Default")
      (node (ref "D3") (pin "1") (pinfunction "A_1") (pintype "passive"))
      (node (ref "R13") (pin "1") (pinfunction "1_1") (pintype "passive"))
      (node (ref "R6") (pin "1") (pinfunction "1_1") (pintype "passive"))
    )
    (net (code "11") (name "Net-(D4-A)") (class "Default")
      (node (ref "D4") (pin "1") (pinfunction "A_1") (pintype "passive"))
      (node (ref "R7") (pin "1") (pinfunction "1_1") (pintype "passive"))
    )
    (net (code "12") (name "Net-(U1-EN)") (class "Default")
      (node (ref "R1") (pin "1") (pinfunction "1_1") (pintype "passive"))
      (node (ref "R3") (pin "1") (pinfunction "1_1") (pintype "passive"))
      (node (ref "R4") (pin "2") (pinfunction "2_2") (pintype "passive"))
      (node (ref "U1") (pin "5") (pinfunction "EN_5") (pintype "passive"))
    )
    (net (code "13") (name "Net-(U1-SW)") (class "Default")
      (node (ref "C4") (pin "1") (pinfunction "1_1") (pintype "passive"))
      (node (ref "L1") (pin "1") (pinfunction "1_1") (pintype "passive"))
      (node (ref "U1") (pin "2") (pinfunction "SW_2") (pintype "passive"))
    )
    (net (code "14") (name "Net-(U1-VBST)") (class "Default")
      (node (ref "C4") (pin "2") (pinfunction "2_2") (pintype "passive"))
      (node (ref "U1") (pin "6") (pinfunction "VBST_6") (pintype "passive"))
    )
    (net (code "15") (name "Net-(U1-VFB)") (class "Default")
      (node (ref "R2") (pin "1") (pinfunction "1_1") (pintype "passive"))
      (node (ref "R5") (pin "1") (pinfunction "1_1") (pintype "passive"))
      (node (ref "U1") (pin "4") (pinfunction "VFB_4") (pintype "passive"))
    )
    (net (code "16") (name "Net-(U26-EN)") (class "Default")
      (node (ref "R236") (pin "1") (pinfunction "1_1") (pintype "passive"))
      (node (ref "R244") (pin "1") (pinfunction "1_1") (pintype "passive"))
      (node (ref "R280") (pin "2") (pinfunction "2_2") (pintype "passive"))
      (node (ref "U26") (pin "5") (pinfunction "EN_5") (pintype "passive"))
    )
    (net (code "17") (name "Net-(U26-SW)") (class "Default")
      (node (ref "C111") (pin "1") (pinfunction "1_1") (pintype "passive"))
      (node (ref "L7") (pin "1") (pinfunction "1_1") (pintype "passive"))
      (node (ref "U26") (pin "2") (pinfunction "SW_2") (pintype "passive"))
    )
    (net (code "18") (name "Net-(U26-VBST)") (class "Default")
      (node (ref "C111") (pin "2") (pinfunction "2_2") (pintype "passive"))
      (node (ref "U26") (pin "6") (pinfunction "VBST_6") (pintype "passive"))
    )
    (net (code "19") (name "Net-(U26-VFB)") (class "Default")
      (node (ref "R243") (pin "1") (pinfunction "1_1") (pintype "passive"))
      (node (ref "R281") (pin "1") (pinfunction "1_1") (pintype "passive"))
      (node (ref "U26") (pin "4") (pinfunction "VFB_4") (pintype "passive"))
    )
    (net (code "20") (name "USB_5V") (class "Default")
      (node (ref "C112") (pin "2") (pinfunction "2_2") (pintype "passive"))
      (node (ref "C126") (pin "2") (pinfunction "2_2") (pintype "passive"))
      (node (ref "C150") (pin "2") (pinfunction "2_2") (pintype "passive"))
      (node (ref "L7") (pin "2") (pinfunction "2_2") (pintype "passive"))
      (node (ref "R243") (pin "2") (pinfunction "2_2") (pintype "passive"))
      (node (ref "R282") (pin "2") (pinfunction "2_2") (pintype "passive"))
      (node (ref "R283") (pin "2") (pinfunction "2_2") (pintype "passive"))
      (node (ref "TP5") (pin "1") (pinfunction "1_1") (pintype "passive"))
    )
    (net (code "21") (name "VCC_RTC") (class "Default")
      (node (ref "D1") (pin "2") (pinfunction "K_2") (pintype "passive"))
      (node (ref "D2") (pin "2") (pinfunction "K_2") (pintype "passive"))
    )
    (net (code "22") (name "VCC_SYS") (class "Default")
      (node (ref "C10") (pin "2") (pinfunction "2_2") (pintype "passive"))
      (node (ref "C11") (pin "2") (pinfunction "2_2") (pintype "passive"))
      (node (ref "C355") (pin "2") (pinfunction "2_2") (pintype "passive"))
      (node (ref "C9") (pin "2") (pinfunction "2_2") (pintype "passive"))
      (node (ref "L1") (pin "2") (pinfunction "2_2") (pintype "passive"))
      (node (ref "R2") (pin "2") (pinfunction "2_2") (pintype "passive"))
      (node (ref "R282") (pin "1") (pinfunction "1_1") (pintype "passive"))
      (node (ref "R283") (pin "1") (pinfunction "1_1") (pintype "passive"))
      (node (ref "TP4") (pin "1") (pinfunction "1_1") (pintype "passive"))
    )
    (net (code "23") (name "unconnected-(M1-Pad52)") (class "Default")
      (node (ref "M1") (pin "52") (pinfunction "52_52") (pintype "passive+no_connect"))
    )
    (net (code "24") (name "unconnected-(M2-Pad52)") (class "Default")
      (node (ref "M2") (pin "52") (pinfunction "52_52") (pintype "passive+no_connect"))
    )
    (net (code "25") (name "unconnected-(M3-Pad52)") (class "Default")
      (node (ref "M3") (pin "52") (pinfunction "52_52") (pintype "passive+no_connect"))
    )
    (net (code "26") (name "unconnected-(M4-Pad52)") (class "Default")
      (node (ref "M4") (pin "52") (pinfunction "52_52") (pintype "passive+no_connect"))
    )
    (net (code "27") (name "unconnected-(M5-Pad52)") (class "Default")
      (node (ref "M5") (pin "52") (pinfunction "52_52") (pintype "passive+no_connect"))
    )
    (net (code "28") (name "unconnected-(M6-Pad52)") (class "Default")
      (node (ref "M6") (pin "52") (pinfunction "52_52") (pintype "passive+no_connect"))
    )
    (net (code "29") (name "unconnected-(M7-Pad52)") (class "Default")
      (node (ref "M7") (pin "52") (pinfunction "52_52") (pintype "passive+no_connect"))
    )
    (net (code "30") (name "unconnected-(M8-Pad52)") (class "Default")
      (node (ref "M8") (pin "52") (pinfunction "52_52") (pintype "passive+no_connect"))
    )
    (net (code "31") (name "unconnected-(R3-Pad2)") (class "Default")
      (node (ref "R3") (pin "2") (pinfunction "2_2") (pintype "passive"))
    )
    (net (code "32") (name "unconnected-(R244-Pad2)") (class "Default")
      (node (ref "R244") (pin "2") (pinfunction "2_2") (pintype "passive"))
    )
  )
)
